# MCU.net
KiCad netlist of a schematic drawn in Altium Designer
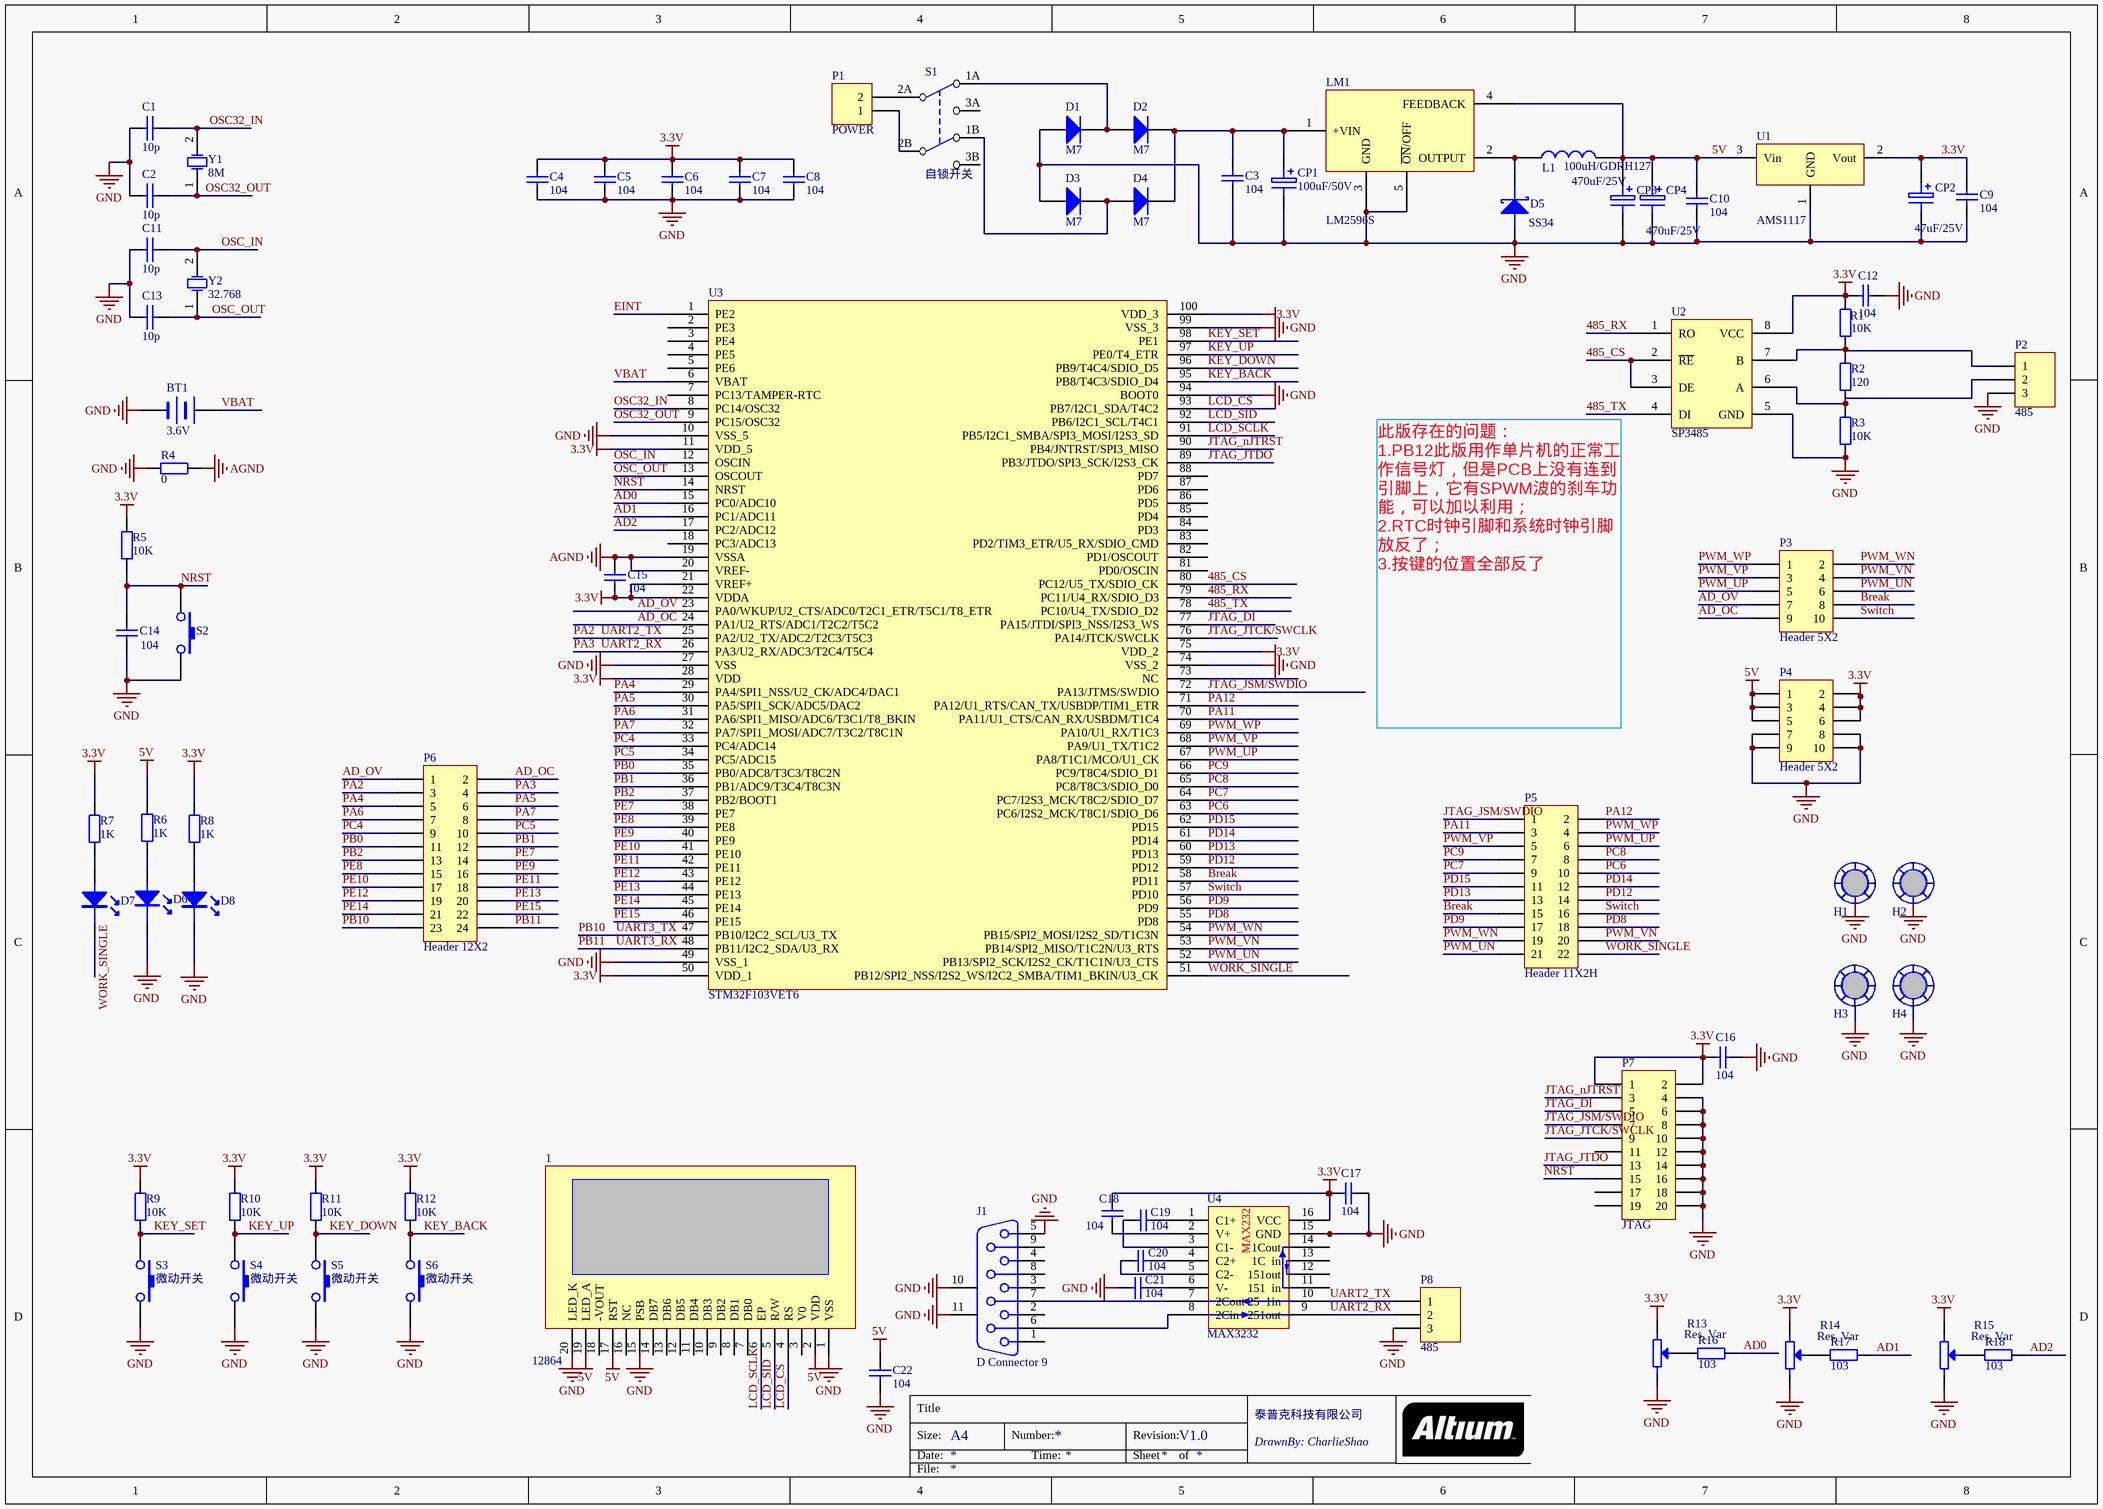
[diagram p0: MCU外围电路.SchDoc]

(export (version "E")
  (design (tool "Eeschema 10.0.6"))
  (components
    (comp (ref "1") (value "12864") (footprint "YX12864B") (libsource (lib "Backup of 杨飞原理库") (part "12864")))
    (comp (ref "BT1")
      (value "3.6V")
      (footprint "CR1220")
      (description "3.6V纽扣电池")
      (libsource (lib "cloudlib") (part "BATTERY"))
    )
    (comp (ref "C1")
      (value "10p")
      (footprint "0805C")
      (description "非极性电容")
      (libsource (lib "cloudlib") (part "Cap"))
    )
    (comp (ref "C2")
      (value "10p")
      (footprint "0805C")
      (description "非极性电容")
      (libsource (lib "cloudlib") (part "Cap"))
    )
    (comp (ref "C3")
      (value "104")
      (footprint "0805C")
      (description "Capacitor")
      (fields (field (name "PUBLISHER") "Altium Limited"))
      (libsource (lib "Miscellaneous Devices") (part "Cap"))
    )
    (comp (ref "C4")
      (value "104")
      (footprint "0805C")
      (description "Capacitor")
      (fields (field (name "PUBLISHER") "Altium Limited"))
      (libsource (lib "Miscellaneous Devices") (part "Cap"))
    )
    (comp (ref "C5")
      (value "104")
      (footprint "0805C")
      (description "Capacitor")
      (fields (field (name "PUBLISHER") "Altium Limited"))
      (libsource (lib "Miscellaneous Devices") (part "Cap"))
    )
    (comp (ref "C6")
      (value "104")
      (footprint "0805C")
      (description "Capacitor")
      (fields (field (name "PUBLISHER") "Altium Limited"))
      (libsource (lib "Miscellaneous Devices") (part "Cap"))
    )
    (comp (ref "C7")
      (value "104")
      (footprint "0805C")
      (description "Capacitor")
      (fields (field (name "PUBLISHER") "Altium Limited"))
      (libsource (lib "Miscellaneous Devices") (part "Cap"))
    )
    (comp (ref "C8")
      (value "104")
      (footprint "0805C")
      (description "Capacitor")
      (fields (field (name "PUBLISHER") "Altium Limited"))
      (libsource (lib "Miscellaneous Devices") (part "Cap"))
    )
    (comp (ref "C9")
      (value "104")
      (footprint "0805C")
      (description "Capacitor")
      (fields (field (name "PUBLISHER") "Altium Limited"))
      (libsource (lib "Miscellaneous Devices") (part "Cap"))
    )
    (comp (ref "C10")
      (value "104")
      (footprint "0805C")
      (description "Capacitor")
      (fields (field (name "PUBLISHER") "Altium Limited"))
      (libsource (lib "Miscellaneous Devices") (part "Cap"))
    )
    (comp (ref "C11")
      (value "10p")
      (footprint "0805C")
      (description "非极性电容")
      (libsource (lib "cloudlib") (part "Cap"))
    )
    (comp (ref "C12")
      (value "104")
      (footprint "0805C")
      (description "Capacitor")
      (fields (field (name "PUBLISHER") "Altium Limited"))
      (libsource (lib "Miscellaneous Devices") (part "Cap"))
    )
    (comp (ref "C13")
      (value "10p")
      (footprint "0805C")
      (description "非极性电容")
      (libsource (lib "cloudlib") (part "Cap"))
    )
    (comp (ref "C14")
      (value "104")
      (footprint "0805C")
      (description "Capacitor")
      (fields (field (name "PUBLISHER") "Altium Limited"))
      (libsource (lib "Miscellaneous Devices") (part "Cap"))
    )
    (comp (ref "C15")
      (value "104")
      (footprint "0805C")
      (description "Capacitor")
      (fields (field (name "PUBLISHER") "Altium Limited"))
      (libsource (lib "Miscellaneous Devices") (part "Cap"))
    )
    (comp (ref "C16")
      (value "104")
      (footprint "0805C")
      (description "Capacitor")
      (fields (field (name "PUBLISHER") "Altium Limited"))
      (libsource (lib "Miscellaneous Devices") (part "Cap"))
    )
    (comp (ref "C17")
      (value "104")
      (footprint "0805C")
      (description "Capacitor")
      (fields (field (name "PUBLISHER") "Altium Limited"))
      (libsource (lib "Miscellaneous Devices") (part "Cap"))
    )
    (comp (ref "C18")
      (value "104")
      (footprint "0805C")
      (description "Capacitor")
      (fields (field (name "PUBLISHER") "Altium Limited"))
      (libsource (lib "Miscellaneous Devices") (part "Cap"))
    )
    (comp (ref "C19")
      (value "104")
      (footprint "0805C")
      (description "Capacitor")
      (fields (field (name "PUBLISHER") "Altium Limited"))
      (libsource (lib "Miscellaneous Devices") (part "Cap"))
    )
    (comp (ref "C20")
      (value "104")
      (footprint "0805C")
      (description "Capacitor")
      (fields (field (name "PUBLISHER") "Altium Limited"))
      (libsource (lib "Miscellaneous Devices") (part "Cap"))
    )
    (comp (ref "C21")
      (value "104")
      (footprint "0805C")
      (description "Capacitor")
      (fields (field (name "PUBLISHER") "Altium Limited"))
      (libsource (lib "Miscellaneous Devices") (part "Cap"))
    )
    (comp (ref "C22")
      (value "104")
      (footprint "0805C")
      (description "Capacitor")
      (fields (field (name "PUBLISHER") "Altium Limited"))
      (libsource (lib "Miscellaneous Devices") (part "Cap"))
    )
    (comp (ref "CP1")
      (value "100uF/50V")
      (footprint "cloudlib:CAP_8X105")
      (description "极性电容")
      (libsource (lib "cloudlib") (part "Cap_Pol"))
    )
    (comp (ref "CP2")
      (value "47uF/25V")
      (footprint "cloudlib:CAP_6.3X5.4")
      (description "极性电容")
      (libsource (lib "cloudlib") (part "Cap_Pol"))
    )
    (comp (ref "CP3")
      (value "470uF/25V")
      (footprint "cloudlib:CAP_10X105")
      (description "极性电容")
      (libsource (lib "cloudlib") (part "Cap_Pol"))
    )
    (comp (ref "CP4")
      (value "470uF/25V")
      (footprint "cloudlib:CAP_10X105")
      (description "极性电容")
      (libsource (lib "cloudlib") (part "Cap_Pol"))
    )
    (comp (ref "D1")
      (value "M7")
      (footprint "SMA")
      (description "Default Diode")
      (fields (field (name "PUBLISHER") "Altium Limited"))
      (libsource (lib "Miscellaneous Devices") (part "Diode"))
    )
    (comp (ref "D2")
      (value "M7")
      (footprint "SMA")
      (description "Default Diode")
      (fields (field (name "PUBLISHER") "Altium Limited"))
      (libsource (lib "Miscellaneous Devices") (part "Diode"))
    )
    (comp (ref "D3")
      (value "M7")
      (footprint "SMA")
      (description "Default Diode")
      (fields (field (name "PUBLISHER") "Altium Limited"))
      (libsource (lib "Miscellaneous Devices") (part "Diode"))
    )
    (comp (ref "D4")
      (value "M7")
      (footprint "SMA")
      (description "Default Diode")
      (fields (field (name "PUBLISHER") "Altium Limited"))
      (libsource (lib "Miscellaneous Devices") (part "Diode"))
    )
    (comp (ref "D5")
      (value "SS34")
      (footprint "cloudlib:SMC")
      (description "肖特基")
      (libsource (lib "cloudlib") (part "Diode_Schottky"))
    )
    (comp (ref "D6") (value "LED") (footprint "cloudlib:LED_0805") (libsource (lib "CCDXPLIB") (part "LED")))
    (comp (ref "D7") (value "LED") (footprint "cloudlib:LED_0805") (libsource (lib "CCDXPLIB") (part "LED")))
    (comp (ref "D8") (value "LED") (footprint "cloudlib:LED_0805") (libsource (lib "CCDXPLIB") (part "LED")))
    (comp (ref "H1") (value "铜柱孔") (footprint "HOLE") (libsource (lib "cloudlib") (part "铜柱孔")))
    (comp (ref "H2") (value "铜柱孔") (footprint "HOLE") (libsource (lib "cloudlib") (part "铜柱孔")))
    (comp (ref "H3") (value "铜柱孔") (footprint "HOLE") (libsource (lib "cloudlib") (part "铜柱孔")))
    (comp (ref "H4") (value "铜柱孔") (footprint "HOLE") (libsource (lib "cloudlib") (part "铜柱孔")))
    (comp (ref "J1")
      (value "D Connector 9")
      (footprint "DSUB1.385-2H9")
      (description "Receptacle Assembly, 9 Position, Right Angle")
      (fields (field (name "PUBLISHER") "Altium Limited"))
      (libsource (lib "Miscellaneous Connectors") (part "D Connector 9"))
    )
    (comp (ref "L1")
      (value "100uH/GDRH127")
      (footprint "cloudlib:SMDRH124/125/127")
      (description "电感")
      (libsource (lib "cloudlib") (part "Inductor"))
    )
    (comp (ref "LM1") (value "LM2596S") (footprint "TO-263S") (libsource (lib "cloudlib") (part "LM2596S")))
    (comp (ref "P1")
      (value "POWER")
      (footprint "cloudlib:3.81-2")
      (description "Header, 2-Pin")
      (fields (field (name "PUBLISHER") "Altium Limited"))
      (libsource (lib "Miscellaneous Connectors") (part "Header 2"))
    )
    (comp (ref "P2")
      (value "485")
      (footprint "cloudlib:SIP3")
      (description "Header, 3-Pin")
      (fields (field (name "PUBLISHER") "Altium Limited"))
      (libsource (lib "Miscellaneous Connectors") (part "MHDR1X3"))
    )
    (comp (ref "P3")
      (value "Header 5X2")
      (footprint "HDR2X5")
      (description "Header, 5-Pin, Dual row")
      (fields (field (name "PUBLISHER") "Altium Limited"))
      (libsource (lib "Miscellaneous Connectors") (part "Header 5X2"))
    )
    (comp (ref "P4")
      (value "Header 5X2")
      (footprint "HDR2X5")
      (description "Header, 5-Pin, Dual row")
      (fields (field (name "PUBLISHER") "Altium Limited"))
      (libsource (lib "Miscellaneous Connectors") (part "Header 5X2"))
    )
    (comp (ref "P5")
      (value "Header 11X2H")
      (footprint "Miscellaneous Connectors:HDR2X11")
      (description "Header, 11-Pin, Dual row, Right Angle")
      (fields (field (name "PUBLISHER") "Altium Limited"))
      (libsource (lib "Miscellaneous Connectors") (part "Header 11X2H"))
    )
    (comp (ref "P6")
      (value "Header 12X2")
      (footprint "HDR2X12")
      (description "Header, 12-Pin, Dual row")
      (fields (field (name "PUBLISHER") "Altium Limited"))
      (libsource (lib "Miscellaneous Connectors") (part "Header 12X2"))
    )
    (comp (ref "P7")
      (value "JTAG")
      (footprint "JTAG20")
      (description "Header, 10-Pin, Dual row")
      (fields (field (name "PUBLISHER") "Altium Limited"))
      (libsource (lib "Miscellaneous Connectors") (part "Header 10X2"))
    )
    (comp (ref "P8")
      (value "485")
      (footprint "cloudlib:SIP3")
      (description "Header, 3-Pin")
      (fields (field (name "PUBLISHER") "Altium Limited"))
      (libsource (lib "Miscellaneous Connectors") (part "MHDR1X3"))
    )
    (comp (ref "R1")
      (value "10K")
      (footprint "0805R")
      (description "Resistor")
      (fields (field (name "PUBLISHER") "Altium Limited"))
      (libsource (lib "") (part "Res2_2"))
    )
    (comp (ref "R2")
      (value "120")
      (footprint "0805R")
      (description "Resistor")
      (fields (field (name "PUBLISHER") "Altium Limited"))
      (libsource (lib "") (part "Res2_2"))
    )
    (comp (ref "R3")
      (value "10K")
      (footprint "0805R")
      (description "Resistor")
      (fields (field (name "PUBLISHER") "Altium Limited"))
      (libsource (lib "") (part "Res2_2"))
    )
    (comp (ref "R4")
      (value "0")
      (footprint "0805R")
      (description "Resistor")
      (fields (field (name "PUBLISHER") "Altium Limited"))
      (libsource (lib "") (part "Res2_1"))
    )
    (comp (ref "R5")
      (value "10K")
      (footprint "0805R")
      (description "Resistor")
      (fields (field (name "PUBLISHER") "Altium Limited"))
      (libsource (lib "") (part "Res2_2"))
    )
    (comp (ref "R6")
      (value "1K")
      (footprint "0805R")
      (description "Resistor")
      (fields (field (name "PUBLISHER") "Altium Limited"))
      (libsource (lib "Miscellaneous Devices") (part "Res2"))
    )
    (comp (ref "R7")
      (value "1K")
      (footprint "0805R")
      (description "Resistor")
      (fields (field (name "PUBLISHER") "Altium Limited"))
      (libsource (lib "Miscellaneous Devices") (part "Res2"))
    )
    (comp (ref "R8")
      (value "1K")
      (footprint "0805R")
      (description "Resistor")
      (fields (field (name "PUBLISHER") "Altium Limited"))
      (libsource (lib "Miscellaneous Devices") (part "Res2"))
    )
    (comp (ref "R9")
      (value "10K")
      (footprint "0805R")
      (description "Resistor")
      (fields (field (name "PUBLISHER") "Altium Limited"))
      (libsource (lib "") (part "Res2_2"))
    )
    (comp (ref "R10")
      (value "10K")
      (footprint "0805R")
      (description "Resistor")
      (fields (field (name "PUBLISHER") "Altium Limited"))
      (libsource (lib "") (part "Res2_2"))
    )
    (comp (ref "R11")
      (value "10K")
      (footprint "0805R")
      (description "Resistor")
      (fields (field (name "PUBLISHER") "Altium Limited"))
      (libsource (lib "") (part "Res2_2"))
    )
    (comp (ref "R12")
      (value "10K")
      (footprint "0805R")
      (description "Resistor")
      (fields (field (name "PUBLISHER") "Altium Limited"))
      (libsource (lib "") (part "Res2_2"))
    )
    (comp (ref "R13")
      (value "Res_Var")
      (footprint "cloudlib:VR1")
      (description "可变电阻")
      (libsource (lib "cloudlib") (part "Res_Var"))
    )
    (comp (ref "R14")
      (value "Res_Var")
      (footprint "cloudlib:VR1")
      (description "可变电阻")
      (libsource (lib "cloudlib") (part "Res_Var"))
    )
    (comp (ref "R15")
      (value "Res_Var")
      (footprint "cloudlib:VR1")
      (description "可变电阻")
      (libsource (lib "cloudlib") (part "Res_Var"))
    )
    (comp (ref "R16")
      (value "103")
      (footprint "cloudlib:0805R")
      (description "Resistor")
      (fields (field (name "PUBLISHER") "Altium Limited"))
      (libsource (lib "") (part "Res2_1"))
    )
    (comp (ref "R17")
      (value "103")
      (footprint "cloudlib:0805R")
      (description "Resistor")
      (fields (field (name "PUBLISHER") "Altium Limited"))
      (libsource (lib "") (part "Res2_1"))
    )
    (comp (ref "R18")
      (value "103")
      (footprint "cloudlib:0805R")
      (description "Resistor")
      (fields (field (name "PUBLISHER") "Altium Limited"))
      (libsource (lib "") (part "Res2_1"))
    )
    (comp (ref "S1") (value "自锁开关") (footprint "cloudlib:自锁开关") (libsource (lib "cloudlib") (part "自锁开关")))
    (comp (ref "S2")
      (value "KEY")
      (footprint "cloudlib:SW_PB - 6.5x4.5")
      (libsource (lib "CCDXPLIB") (part "KEY"))
    )
    (comp (ref "S3")
      (value "微动开关")
      (footprint "cloudlib:SW_PB - 6.5x4.5")
      (libsource (lib "开关") (part "微动开关"))
    )
    (comp (ref "S4")
      (value "微动开关")
      (footprint "cloudlib:SW_PB - 6.5x4.5")
      (libsource (lib "开关") (part "微动开关"))
    )
    (comp (ref "S5")
      (value "微动开关")
      (footprint "cloudlib:SW_PB - 6.5x4.5")
      (libsource (lib "开关") (part "微动开关"))
    )
    (comp (ref "S6")
      (value "微动开关")
      (footprint "cloudlib:SW_PB - 6.5x4.5")
      (libsource (lib "开关") (part "微动开关"))
    )
    (comp (ref "U1")
      (value "AMS1117")
      (footprint "SOT223")
      (description "三端稳压器件")
      (libsource (lib "cloudlib") (part "AMS1117"))
    )
    (comp (ref "U2") (value "SP3485") (footprint "myall:SO-8") (libsource (lib "cloudlib") (part "MAX485")))
    (comp (ref "U3")
      (value "STM32F103VET6")
      (footprint "cloudlib:LQFP100")
      (libsource (lib "cloudlib") (part "STM32F103VET6"))
    )
    (comp (ref "U4")
      (value "MAX3232")
      (footprint "cloudlib:SO-16")
      (libsource (lib "单片机及相关") (part "MAX232"))
    )
    (comp (ref "Y1")
      (value "8M")
      (footprint "XTAL2")
      (description "Crystal Oscillator")
      (fields (field (name "PUBLISHER") "Altium Limited"))
      (libsource (lib "cloudlib") (part "XTAL"))
    )
    (comp (ref "Y2")
      (value "32.768")
      (footprint "XTAL1")
      (description "Crystal Oscillator")
      (fields (field (name "PUBLISHER") "Altium Limited"))
      (libsource (lib "cloudlib") (part "XTAL"))
    )
  )
  (nets
    (net (code "1") (name "/485_CS") (class "Default")
      (node (ref "U2") (pin "2") (pinfunction "~{RE}_2") (pintype "open_emitter"))
      (node (ref "U2") (pin "3") (pinfunction "DE_3") (pintype "open_emitter"))
      (node (ref "U3") (pin "80") (pinfunction "PC12/U5_TX/SDIO_CK_80") (pintype "passive"))
    )
    (net (code "2") (name "/485_RX") (class "Default")
      (node (ref "U2") (pin "1") (pinfunction "RO_1") (pintype "open_emitter"))
      (node (ref "U3") (pin "79") (pinfunction "PC11/U4_RX/SDIO_D3_79") (pintype "passive"))
    )
    (net (code "3") (name "/485_TX") (class "Default")
      (node (ref "U2") (pin "4") (pinfunction "DI_4") (pintype "open_emitter"))
      (node (ref "U3") (pin "78") (pinfunction "PC10/U4_TX/SDIO_D2_78") (pintype "passive"))
    )
    (net (code "4") (name "/AD0") (class "Default")
      (node (ref "R16") (pin "1") (pinfunction "1_1") (pintype "passive"))
      (node (ref "U3") (pin "15") (pinfunction "PC0/ADC10_15") (pintype "passive"))
    )
    (net (code "5") (name "/AD1") (class "Default")
      (node (ref "R17") (pin "1") (pinfunction "1_1") (pintype "passive"))
      (node (ref "U3") (pin "16") (pinfunction "PC1/ADC11_16") (pintype "passive"))
    )
    (net (code "6") (name "/AD2") (class "Default")
      (node (ref "R18") (pin "1") (pinfunction "1_1") (pintype "passive"))
      (node (ref "U3") (pin "17") (pinfunction "PC2/ADC12_17") (pintype "passive"))
    )
    (net (code "7") (name "/AD_OC") (class "Default")
      (node (ref "P3") (pin "9") (pinfunction "9_9") (pintype "passive"))
      (node (ref "P6") (pin "2") (pinfunction "2_2") (pintype "passive"))
      (node (ref "U3") (pin "24") (pinfunction "PA1/U2_RTS/ADC1/T2C2/T5C2_24") (pintype "passive"))
    )
    (net (code "8") (name "/AD_OV") (class "Default")
      (node (ref "P3") (pin "7") (pinfunction "7_7") (pintype "passive"))
      (node (ref "P6") (pin "1") (pinfunction "1_1") (pintype "passive"))
      (node (ref "U3") (pin "23") (pinfunction "PA0/WKUP/U2_CTS/ADC0/T2C1_ETR/T5C1/T8_ETR_23") (pintype "passive"))
    )
    (net (code "9") (name "/Break") (class "Default")
      (node (ref "P3") (pin "8") (pinfunction "8_8") (pintype "passive"))
      (node (ref "P5") (pin "15") (pinfunction "15_15") (pintype "passive"))
      (node (ref "U3") (pin "58") (pinfunction "PD11_58") (pintype "passive"))
    )
    (net (code "10") (name "/EINT") (class "Default")
      (node (ref "U3") (pin "1") (pinfunction "PE2_1") (pintype "passive"))
    )
    (net (code "11") (name "/JTAG_DI") (class "Default")
      (node (ref "P7") (pin "5") (pinfunction "5_5") (pintype "passive"))
      (node (ref "U3") (pin "77") (pinfunction "PA15/JTDI/SPI3_NSS/I2S3_WS_77") (pintype "passive"))
    )
    (net (code "12") (name "/JTAG_JSM{slash}SWDIO") (class "Default")
      (node (ref "P5") (pin "1") (pinfunction "1_1") (pintype "passive"))
      (node (ref "P7") (pin "7") (pinfunction "7_7") (pintype "passive"))
      (node (ref "U3") (pin "72") (pinfunction "PA13/JTMS/SWDIO_72") (pintype "passive"))
    )
    (net (code "13") (name "/JTAG_JTCK{slash}SWCLK") (class "Default")
      (node (ref "P7") (pin "9") (pinfunction "9_9") (pintype "passive"))
      (node (ref "U3") (pin "76") (pinfunction "PA14/JTCK/SWCLK_76") (pintype "passive"))
    )
    (net (code "14") (name "/JTAG_JTDO") (class "Default")
      (node (ref "P7") (pin "13") (pinfunction "13_13") (pintype "passive"))
      (node (ref "U3") (pin "89") (pinfunction "PB3/JTDO/SPI3_SCK/I2S3_CK_89") (pintype "passive"))
    )
    (net (code "15") (name "/JTAG_nJTRST") (class "Default")
      (node (ref "P7") (pin "3") (pinfunction "3_3") (pintype "passive"))
      (node (ref "U3") (pin "90") (pinfunction "PB4/JNTRST/SPI3_MISO_90") (pintype "passive"))
    )
    (net (code "16") (name "/KEY_BACK") (class "Default")
      (node (ref "R12") (pin "1") (pinfunction "1_1") (pintype "passive"))
      (node (ref "S6") (pin "1") (pinfunction "1_1") (pintype "passive"))
      (node (ref "U3") (pin "95") (pinfunction "PB8/T4C3/SDIO_D4_95") (pintype "passive"))
    )
    (net (code "17") (name "/KEY_DOWN") (class "Default")
      (node (ref "R11") (pin "1") (pinfunction "1_1") (pintype "passive"))
      (node (ref "S5") (pin "1") (pinfunction "1_1") (pintype "passive"))
      (node (ref "U3") (pin "96") (pinfunction "PB9/T4C4/SDIO_D5_96") (pintype "passive"))
    )
    (net (code "18") (name "/KEY_SET") (class "Default")
      (node (ref "R9") (pin "1") (pinfunction "1_1") (pintype "passive"))
      (node (ref "S3") (pin "1") (pinfunction "1_1") (pintype "passive"))
      (node (ref "U3") (pin "98") (pinfunction "PE1_98") (pintype "passive"))
    )
    (net (code "19") (name "/KEY_UP") (class "Default")
      (node (ref "R10") (pin "1") (pinfunction "1_1") (pintype "passive"))
      (node (ref "S4") (pin "1") (pinfunction "1_1") (pintype "passive"))
      (node (ref "U3") (pin "97") (pinfunction "PE0/T4_ETR_97") (pintype "passive"))
    )
    (net (code "20") (name "/LCD_CS") (class "Default")
      (node (ref "1") (pin "4") (pinfunction "RS_4") (pintype "passive"))
      (node (ref "U3") (pin "93") (pinfunction "PB7/I2C1_SDA/T4C2_93") (pintype "passive"))
    )
    (net (code "21") (name "/LCD_SCLK") (class "Default")
      (node (ref "1") (pin "6") (pinfunction "EP_6") (pintype "passive"))
      (node (ref "U3") (pin "91") (pinfunction "PB5/I2C1_SMBA/SPI3_MOSI/I2S3_SD_91") (pintype "passive"))
    )
    (net (code "22") (name "/LCD_SID") (class "Default")
      (node (ref "1") (pin "5") (pinfunction "R/W_5") (pintype "passive"))
      (node (ref "U3") (pin "92") (pinfunction "PB6/I2C1_SCL/T4C1_92") (pintype "passive"))
    )
    (net (code "23") (name "/NRST") (class "Default")
      (node (ref "C14") (pin "2") (pinfunction "2_2") (pintype "passive"))
      (node (ref "P7") (pin "15") (pinfunction "15_15") (pintype "passive"))
      (node (ref "R5") (pin "1") (pinfunction "1_1") (pintype "passive"))
      (node (ref "S2") (pin "1") (pinfunction "1_1") (pintype "passive"))
      (node (ref "U3") (pin "14") (pinfunction "NRST_14") (pintype "passive"))
    )
    (net (code "24") (name "/OSC32_IN") (class "Default")
      (node (ref "C1") (pin "2") (pinfunction "2_2") (pintype "passive"))
      (node (ref "U3") (pin "8") (pinfunction "PC14/OSC32_8") (pintype "passive"))
      (node (ref "Y1") (pin "2") (pinfunction "OSC2_2") (pintype "passive"))
    )
    (net (code "25") (name "/OSC32_OUT") (class "Default")
      (node (ref "C2") (pin "2") (pinfunction "2_2") (pintype "passive"))
      (node (ref "U3") (pin "9") (pinfunction "PC15/OSC32_9") (pintype "passive"))
      (node (ref "Y1") (pin "1") (pinfunction "OSC1_1") (pintype "passive"))
    )
    (net (code "26") (name "/OSC_IN") (class "Default")
      (node (ref "C11") (pin "2") (pinfunction "2_2") (pintype "passive"))
      (node (ref "U3") (pin "12") (pinfunction "OSCIN_12") (pintype "passive"))
      (node (ref "Y2") (pin "2") (pinfunction "OSC2_2") (pintype "passive"))
    )
    (net (code "27") (name "/OSC_OUT") (class "Default")
      (node (ref "C13") (pin "2") (pinfunction "2_2") (pintype "passive"))
      (node (ref "U3") (pin "13") (pinfunction "OSCOUT_13") (pintype "passive"))
      (node (ref "Y2") (pin "1") (pinfunction "OSC1_1") (pintype "passive"))
    )
    (net (code "28") (name "/PA2") (class "Default")
      (node (ref "P6") (pin "3") (pinfunction "3_3") (pintype "passive"))
      (node (ref "P8") (pin "1") (pinfunction "1_1") (pintype "passive"))
      (node (ref "U3") (pin "25") (pinfunction "PA2/U2_TX/ADC2/T2C3/T5C3_25") (pintype "passive"))
      (node (ref "U4") (pin "10") (pinfunction "25__1in_10") (pintype "passive"))
    )
    (net (code "29") (name "/PA3") (class "Default")
      (node (ref "P6") (pin "4") (pinfunction "4_4") (pintype "passive"))
      (node (ref "P8") (pin "2") (pinfunction "2_2") (pintype "passive"))
      (node (ref "U3") (pin "26") (pinfunction "PA3/U2_RX/ADC3/T2C4/T5C4_26") (pintype "passive"))
      (node (ref "U4") (pin "9") (pinfunction "251out_9") (pintype "passive"))
    )
    (net (code "30") (name "/PA4") (class "Default")
      (node (ref "P6") (pin "5") (pinfunction "5_5") (pintype "passive"))
      (node (ref "U3") (pin "29") (pinfunction "PA4/SPI1_NSS/U2_CK/ADC4/DAC1_29") (pintype "passive"))
    )
    (net (code "31") (name "/PA5") (class "Default")
      (node (ref "P6") (pin "6") (pinfunction "6_6") (pintype "passive"))
      (node (ref "U3") (pin "30") (pinfunction "PA5/SPI1_SCK/ADC5/DAC2_30") (pintype "passive"))
    )
    (net (code "32") (name "/PA6") (class "Default")
      (node (ref "P6") (pin "7") (pinfunction "7_7") (pintype "passive"))
      (node (ref "U3") (pin "31") (pinfunction "PA6/SPI1_MISO/ADC6/T3C1/T8_BKIN_31") (pintype "passive"))
    )
    (net (code "33") (name "/PA7") (class "Default")
      (node (ref "P6") (pin "8") (pinfunction "8_8") (pintype "passive"))
      (node (ref "U3") (pin "32") (pinfunction "PA7/SPI1_MOSI/ADC7/T3C2/T8C1N_32") (pintype "passive"))
    )
    (net (code "34") (name "/PA11") (class "Default")
      (node (ref "P5") (pin "3") (pinfunction "3_3") (pintype "passive"))
      (node (ref "U3") (pin "70") (pinfunction "PA11/U1_CTS/CAN_RX/USBDM/T1C4_70") (pintype "passive"))
    )
    (net (code "35") (name "/PA12") (class "Default")
      (node (ref "P5") (pin "2") (pinfunction "2_2") (pintype "passive"))
      (node (ref "U3") (pin "71") (pinfunction "PA12/U1_RTS/CAN_TX/USBDP/TIM1_ETR_71") (pintype "passive"))
    )
    (net (code "36") (name "/PB0") (class "Default")
      (node (ref "P6") (pin "11") (pinfunction "11_11") (pintype "passive"))
      (node (ref "U3") (pin "35") (pinfunction "PB0/ADC8/T3C3/T8C2N_35") (pintype "passive"))
    )
    (net (code "37") (name "/PB1") (class "Default")
      (node (ref "P6") (pin "12") (pinfunction "12_12") (pintype "passive"))
      (node (ref "U3") (pin "36") (pinfunction "PB1/ADC9/T3C4/T8C3N_36") (pintype "passive"))
    )
    (net (code "38") (name "/PB2") (class "Default")
      (node (ref "P6") (pin "13") (pinfunction "13_13") (pintype "passive"))
      (node (ref "U3") (pin "37") (pinfunction "PB2/BOOT1_37") (pintype "passive"))
    )
    (net (code "39") (name "/PB10") (class "Default")
      (node (ref "P6") (pin "23") (pinfunction "23_23") (pintype "passive"))
      (node (ref "U3") (pin "47") (pinfunction "PB10/I2C2_SCL/U3_TX_47") (pintype "passive"))
    )
    (net (code "40") (name "/PB11") (class "Default")
      (node (ref "P6") (pin "24") (pinfunction "24_24") (pintype "passive"))
      (node (ref "U3") (pin "48") (pinfunction "PB11/I2C2_SDA/U3_RX_48") (pintype "passive"))
    )
    (net (code "41") (name "/PC4") (class "Default")
      (node (ref "P6") (pin "9") (pinfunction "9_9") (pintype "passive"))
      (node (ref "U3") (pin "33") (pinfunction "PC4/ADC14_33") (pintype "passive"))
    )
    (net (code "42") (name "/PC5") (class "Default")
      (node (ref "P6") (pin "10") (pinfunction "10_10") (pintype "passive"))
      (node (ref "U3") (pin "34") (pinfunction "PC5/ADC15_34") (pintype "passive"))
    )
    (net (code "43") (name "/PC6") (class "Default")
      (node (ref "P5") (pin "10") (pinfunction "10_10") (pintype "passive"))
      (node (ref "U3") (pin "63") (pinfunction "PC6/I2S2_MCK/T8C1/SDIO_D6_63") (pintype "passive"))
    )
    (net (code "44") (name "/PC7") (class "Default")
      (node (ref "P5") (pin "9") (pinfunction "9_9") (pintype "passive"))
      (node (ref "U3") (pin "64") (pinfunction "PC7/I2S3_MCK/T8C2/SDIO_D7_64") (pintype "passive"))
    )
    (net (code "45") (name "/PC8") (class "Default")
      (node (ref "P5") (pin "8") (pinfunction "8_8") (pintype "passive"))
      (node (ref "U3") (pin "65") (pinfunction "PC8/T8C3/SDIO_D0_65") (pintype "passive"))
    )
    (net (code "46") (name "/PC9") (class "Default")
      (node (ref "P5") (pin "7") (pinfunction "7_7") (pintype "passive"))
      (node (ref "U3") (pin "66") (pinfunction "PC9/T8C4/SDIO_D1_66") (pintype "passive"))
    )
    (net (code "47") (name "/PD8") (class "Default")
      (node (ref "P5") (pin "18") (pinfunction "18_18") (pintype "passive"))
      (node (ref "U3") (pin "55") (pinfunction "PD8_55") (pintype "passive"))
    )
    (net (code "48") (name "/PD9") (class "Default")
      (node (ref "P5") (pin "17") (pinfunction "17_17") (pintype "passive"))
      (node (ref "U3") (pin "56") (pinfunction "PD9_56") (pintype "passive"))
    )
    (net (code "49") (name "/PD12") (class "Default")
      (node (ref "P5") (pin "14") (pinfunction "14_14") (pintype "passive"))
      (node (ref "U3") (pin "59") (pinfunction "PD12_59") (pintype "passive"))
    )
    (net (code "50") (name "/PD13") (class "Default")
      (node (ref "P5") (pin "13") (pinfunction "13_13") (pintype "passive"))
      (node (ref "U3") (pin "60") (pinfunction "PD13_60") (pintype "passive"))
    )
    (net (code "51") (name "/PD14") (class "Default")
      (node (ref "P5") (pin "12") (pinfunction "12_12") (pintype "passive"))
      (node (ref "U3") (pin "61") (pinfunction "PD14_61") (pintype "passive"))
    )
    (net (code "52") (name "/PD15") (class "Default")
      (node (ref "P5") (pin "11") (pinfunction "11_11") (pintype "passive"))
      (node (ref "U3") (pin "62") (pinfunction "PD15_62") (pintype "passive"))
    )
    (net (code "53") (name "/PE7") (class "Default")
      (node (ref "P6") (pin "14") (pinfunction "14_14") (pintype "passive"))
      (node (ref "U3") (pin "38") (pinfunction "PE7_38") (pintype "passive"))
    )
    (net (code "54") (name "/PE8") (class "Default")
      (node (ref "P6") (pin "15") (pinfunction "15_15") (pintype "passive"))
      (node (ref "U3") (pin "39") (pinfunction "PE8_39") (pintype "passive"))
    )
    (net (code "55") (name "/PE9") (class "Default")
      (node (ref "P6") (pin "16") (pinfunction "16_16") (pintype "passive"))
      (node (ref "U3") (pin "40") (pinfunction "PE9_40") (pintype "passive"))
    )
    (net (code "56") (name "/PE10") (class "Default")
      (node (ref "P6") (pin "17") (pinfunction "17_17") (pintype "passive"))
      (node (ref "U3") (pin "41") (pinfunction "PE10_41") (pintype "passive"))
    )
    (net (code "57") (name "/PE11") (class "Default")
      (node (ref "P6") (pin "18") (pinfunction "18_18") (pintype "passive"))
      (node (ref "U3") (pin "42") (pinfunction "PE11_42") (pintype "passive"))
    )
    (net (code "58") (name "/PE12") (class "Default")
      (node (ref "P6") (pin "19") (pinfunction "19_19") (pintype "passive"))
      (node (ref "U3") (pin "43") (pinfunction "PE12_43") (pintype "passive"))
    )
    (net (code "59") (name "/PE13") (class "Default")
      (node (ref "P6") (pin "20") (pinfunction "20_20") (pintype "passive"))
      (node (ref "U3") (pin "44") (pinfunction "PE13_44") (pintype "passive"))
    )
    (net (code "60") (name "/PE14") (class "Default")
      (node (ref "P6") (pin "21") (pinfunction "21_21") (pintype "passive"))
      (node (ref "U3") (pin "45") (pinfunction "PE14_45") (pintype "passive"))
    )
    (net (code "61") (name "/PE15") (class "Default")
      (node (ref "P6") (pin "22") (pinfunction "22_22") (pintype "passive"))
      (node (ref "U3") (pin "46") (pinfunction "PE15_46") (pintype "passive"))
    )
    (net (code "62") (name "/PWM_UN") (class "Default")
      (node (ref "P3") (pin "6") (pinfunction "6_6") (pintype "passive"))
      (node (ref "P5") (pin "21") (pinfunction "21_21") (pintype "passive"))
      (node (ref "U3") (pin "52") (pinfunction "PB13/SPI2_SCK/I2S2_CK/T1C1N/U3_CTS_52") (pintype "passive"))
    )
    (net (code "63") (name "/PWM_UP") (class "Default")
      (node (ref "P3") (pin "5") (pinfunction "5_5") (pintype "passive"))
      (node (ref "P5") (pin "6") (pinfunction "6_6") (pintype "passive"))
      (node (ref "U3") (pin "67") (pinfunction "PA8/T1C1/MCO/U1_CK_67") (pintype "passive"))
    )
    (net (code "64") (name "/PWM_VN") (class "Default")
      (node (ref "P3") (pin "4") (pinfunction "4_4") (pintype "passive"))
      (node (ref "P5") (pin "20") (pinfunction "20_20") (pintype "passive"))
      (node (ref "U3") (pin "53") (pinfunction "PB14/SPI2_MISO/T1C2N/U3_RTS_53") (pintype "passive"))
    )
    (net (code "65") (name "/PWM_VP") (class "Default")
      (node (ref "P3") (pin "3") (pinfunction "3_3") (pintype "passive"))
      (node (ref "P5") (pin "5") (pinfunction "5_5") (pintype "passive"))
      (node (ref "U3") (pin "68") (pinfunction "PA9/U1_TX/T1C2_68") (pintype "passive"))
    )
    (net (code "66") (name "/PWM_WN") (class "Default")
      (node (ref "P3") (pin "2") (pinfunction "2_2") (pintype "passive"))
      (node (ref "P5") (pin "19") (pinfunction "19_19") (pintype "passive"))
      (node (ref "U3") (pin "54") (pinfunction "PB15/SPI2_MOSI/I2S2_SD/T1C3N_54") (pintype "passive"))
    )
    (net (code "67") (name "/PWM_WP") (class "Default")
      (node (ref "P3") (pin "1") (pinfunction "1_1") (pintype "passive"))
      (node (ref "P5") (pin "4") (pinfunction "4_4") (pintype "passive"))
      (node (ref "U3") (pin "69") (pinfunction "PA10/U1_RX/T1C3_69") (pintype "passive"))
    )
    (net (code "68") (name "/Switch") (class "Default")
      (node (ref "P3") (pin "10") (pinfunction "10_10") (pintype "passive"))
      (node (ref "P5") (pin "16") (pinfunction "16_16") (pintype "passive"))
      (node (ref "U3") (pin "57") (pinfunction "PD10_57") (pintype "passive"))
    )
    (net (code "69") (name "/VBAT") (class "Default")
      (node (ref "BT1") (pin "1") (pinfunction "+_1") (pintype "passive"))
      (node (ref "U3") (pin "6") (pinfunction "VBAT_6") (pintype "passive"))
    )
    (net (code "70") (name "/WORK_SINGLE") (class "Default")
      (node (ref "P5") (pin "22") (pinfunction "22_22") (pintype "passive"))
      (node (ref "U3") (pin "51") (pinfunction "PB12/SPI2_NSS/I2S2_WS/I2C2_SMBA/TIM1_BKIN/U3_CK_51") (pintype "passive"))
    )
    (net (code "71") (name "3.3V") (class "Default")
      (node (ref "C12") (pin "1") (pinfunction "1_1") (pintype "passive"))
      (node (ref "C15") (pin "2") (pinfunction "2_2") (pintype "passive"))
      (node (ref "C16") (pin "1") (pinfunction "1_1") (pintype "passive"))
      (node (ref "C17") (pin "2") (pinfunction "2_2") (pintype "passive"))
      (node (ref "C18") (pin "2") (pinfunction "2_2") (pintype "passive"))
      (node (ref "C4") (pin "1") (pinfunction "1_1") (pintype "passive"))
      (node (ref "C5") (pin "1") (pinfunction "1_1") (pintype "passive"))
      (node (ref "C6") (pin "1") (pinfunction "1_1") (pintype "passive"))
      (node (ref "C7") (pin "1") (pinfunction "1_1") (pintype "passive"))
      (node (ref "C8") (pin "1") (pinfunction "1_1") (pintype "passive"))
      (node (ref "C9") (pin "1") (pinfunction "1_1") (pintype "passive"))
      (node (ref "CP2") (pin "1") (pinfunction "1_1") (pintype "passive"))
      (node (ref "P4") (pin "2") (pinfunction "2_2") (pintype "passive"))
      (node (ref "P4") (pin "4") (pinfunction "4_4") (pintype "passive"))
      (node (ref "P4") (pin "6") (pinfunction "6_6") (pintype "passive"))
      (node (ref "P7") (pin "1") (pinfunction "1_1") (pintype "passive"))
      (node (ref "P7") (pin "2") (pinfunction "2_2") (pintype "passive"))
      (node (ref "R1") (pin "2") (pinfunction "2_2") (pintype "passive"))
      (node (ref "R10") (pin "2") (pinfunction "2_2") (pintype "passive"))
      (node (ref "R11") (pin "2") (pinfunction "2_2") (pintype "passive"))
      (node (ref "R12") (pin "2") (pinfunction "2_2") (pintype "passive"))
      (node (ref "R13") (pin "1") (pinfunction "1_1") (pintype "passive"))
      (node (ref "R14") (pin "1") (pinfunction "1_1") (pintype "passive"))
      (node (ref "R15") (pin "1") (pinfunction "1_1") (pintype "passive"))
      (node (ref "R5") (pin "2") (pinfunction "2_2") (pintype "passive"))
      (node (ref "R7") (pin "1") (pinfunction "1_1") (pintype "passive"))
      (node (ref "R8") (pin "1") (pinfunction "1_1") (pintype "passive"))
      (node (ref "R9") (pin "2") (pinfunction "2_2") (pintype "passive"))
      (node (ref "U1") (pin "2") (pinfunction "Vout_2") (pintype "passive"))
      (node (ref "U2") (pin "8") (pinfunction "VCC_8") (pintype "passive"))
      (node (ref "U3") (pin "100") (pinfunction "VDD_3_100") (pintype "passive"))
      (node (ref "U3") (pin "11") (pinfunction "VDD_5_11") (pintype "passive"))
      (node (ref "U3") (pin "21") (pinfunction "VREF+_21") (pintype "passive"))
      (node (ref "U3") (pin "22") (pinfunction "VDDA_22") (pintype "passive"))
      (node (ref "U3") (pin "28") (pinfunction "VDD_28") (pintype "passive"))
      (node (ref "U3") (pin "50") (pinfunction "VDD_1_50") (pintype "passive"))
      (node (ref "U3") (pin "75") (pinfunction "VDD_2_75") (pintype "passive"))
      (node (ref "U4") (pin "16") (pinfunction "VCC_16") (pintype "passive"))
    )
    (net (code "72") (name "5V") (class "Default")
      (node (ref "1") (pin "17") (pinfunction "RST_17") (pintype "passive"))
      (node (ref "1") (pin "19") (pinfunction "LED_A_19") (pintype "passive"))
      (node (ref "1") (pin "2") (pinfunction "VDD_2") (pintype "passive"))
      (node (ref "C10") (pin "1") (pinfunction "1_1") (pintype "passive"))
      (node (ref "C22") (pin "2") (pinfunction "2_2") (pintype "passive"))
      (node (ref "CP3") (pin "1") (pinfunction "1_1") (pintype "passive"))
      (node (ref "CP4") (pin "1") (pinfunction "1_1") (pintype "passive"))
      (node (ref "L1") (pin "2") (pinfunction "2_2") (pintype "passive"))
      (node (ref "LM1") (pin "4") (pinfunction "FEEDBACK_4") (pintype "passive"))
      (node (ref "P4") (pin "1") (pinfunction "1_1") (pintype "passive"))
      (node (ref "P4") (pin "3") (pinfunction "3_3") (pintype "passive"))
      (node (ref "P4") (pin "5") (pinfunction "5_5") (pintype "passive"))
      (node (ref "R6") (pin "1") (pinfunction "1_1") (pintype "passive"))
      (node (ref "U1") (pin "3") (pinfunction "Vin_3") (pintype "passive"))
    )
    (net (code "73") (name "AGND") (class "Default")
      (node (ref "C15") (pin "1") (pinfunction "1_1") (pintype "passive"))
      (node (ref "R4") (pin "1") (pinfunction "1_1") (pintype "passive"))
      (node (ref "U3") (pin "19") (pinfunction "VSSA_19") (pintype "passive"))
      (node (ref "U3") (pin "20") (pinfunction "VREF-_20") (pintype "passive"))
    )
    (net (code "74") (name "GND") (class "Default")
      (node (ref "1") (pin "1") (pinfunction "VSS_1") (pintype "passive"))
      (node (ref "1") (pin "15") (pinfunction "PSB_15") (pintype "passive"))
      (node (ref "1") (pin "20") (pinfunction "LED_K_20") (pintype "passive"))
      (node (ref "BT1") (pin "2") (pinfunction "-_2") (pintype "passive"))
      (node (ref "C1") (pin "1") (pinfunction "1_1") (pintype "passive"))
      (node (ref "C10") (pin "2") (pinfunction "2_2") (pintype "passive"))
      (node (ref "C11") (pin "1") (pinfunction "1_1") (pintype "passive"))
      (node (ref "C12") (pin "2") (pinfunction "2_2") (pintype "passive"))
      (node (ref "C13") (pin "1") (pinfunction "1_1") (pintype "passive"))
      (node (ref "C14") (pin "1") (pinfunction "1_1") (pintype "passive"))
      (node (ref "C16") (pin "2") (pinfunction "2_2") (pintype "passive"))
      (node (ref "C17") (pin "1") (pinfunction "1_1") (pintype "passive"))
      (node (ref "C2") (pin "1") (pinfunction "1_1") (pintype "passive"))
      (node (ref "C21") (pin "2") (pinfunction "2_2") (pintype "passive"))
      (node (ref "C22") (pin "1") (pinfunction "1_1") (pintype "passive"))
      (node (ref "C3") (pin "2") (pinfunction "2_2") (pintype "passive"))
      (node (ref "C4") (pin "2") (pinfunction "2_2") (pintype "passive"))
      (node (ref "C5") (pin "2") (pinfunction "2_2") (pintype "passive"))
      (node (ref "C6") (pin "2") (pinfunction "2_2") (pintype "passive"))
      (node (ref "C7") (pin "2") (pinfunction "2_2") (pintype "passive"))
      (node (ref "C8") (pin "2") (pinfunction "2_2") (pintype "passive"))
      (node (ref "C9") (pin "2") (pinfunction "2_2") (pintype "passive"))
      (node (ref "CP1") (pin "2") (pinfunction "2_2") (pintype "passive"))
      (node (ref "CP2") (pin "2") (pinfunction "2_2") (pintype "passive"))
      (node (ref "CP3") (pin "2") (pinfunction "2_2") (pintype "passive"))
      (node (ref "CP4") (pin "2") (pinfunction "2_2") (pintype "passive"))
      (node (ref "D1") (pin "1") (pinfunction "A_1") (pintype "passive"))
      (node (ref "D3") (pin "1") (pinfunction "A_1") (pintype "passive"))
      (node (ref "D5") (pin "1") (pinfunction "A_1") (pintype "passive"))
      (node (ref "D6") (pin "2") (pinfunction "2_2") (pintype "passive"))
      (node (ref "D8") (pin "2") (pinfunction "2_2") (pintype "passive"))
      (node (ref "H1") (pin "0") (pinfunction "0_0") (pintype "passive"))
      (node (ref "H2") (pin "0") (pinfunction "0_0") (pintype "passive"))
      (node (ref "H3") (pin "0") (pinfunction "0_0") (pintype "passive"))
      (node (ref "H4") (pin "0") (pinfunction "0_0") (pintype "passive"))
      (node (ref "J1") (pin "10") (pinfunction "MH1_10") (pintype "passive"))
      (node (ref "J1") (pin "11") (pinfunction "MH2_11") (pintype "passive"))
      (node (ref "J1") (pin "5") (pinfunction "5_5") (pintype "passive"))
      (node (ref "LM1") (pin "3") (pinfunction "GND_3") (pintype "passive"))
      (node (ref "LM1") (pin "5") (pinfunction "~{ON}/OFF_5") (pintype "passive"))
      (node (ref "P2") (pin "3") (pinfunction "3_3") (pintype "passive"))
      (node (ref "P4") (pin "10") (pinfunction "10_10") (pintype "passive"))
      (node (ref "P4") (pin "7") (pinfunction "7_7") (pintype "passive"))
      (node (ref "P4") (pin "8") (pinfunction "8_8") (pintype "passive"))
      (node (ref "P4") (pin "9") (pinfunction "9_9") (pintype "passive"))
      (node (ref "P7") (pin "10") (pinfunction "10_10") (pintype "passive"))
      (node (ref "P7") (pin "12") (pinfunction "12_12") (pintype "passive"))
      (node (ref "P7") (pin "14") (pinfunction "14_14") (pintype "passive"))
      (node (ref "P7") (pin "16") (pinfunction "16_16") (pintype "passive"))
      (node (ref "P7") (pin "18") (pinfunction "18_18") (pintype "passive"))
      (node (ref "P7") (pin "20") (pinfunction "20_20") (pintype "passive"))
      (node (ref "P7") (pin "4") (pinfunction "4_4") (pintype "passive"))
      (node (ref "P7") (pin "6") (pinfunction "6_6") (pintype "passive"))
      (node (ref "P7") (pin "8") (pinfunction "8_8") (pintype "passive"))
      (node (ref "P8") (pin "3") (pinfunction "3_3") (pintype "passive"))
      (node (ref "R13") (pin "3") (pinfunction "2_3") (pintype "passive"))
      (node (ref "R14") (pin "3") (pinfunction "2_3") (pintype "passive"))
      (node (ref "R15") (pin "3") (pinfunction "2_3") (pintype "passive"))
      (node (ref "R3") (pin "1") (pinfunction "1_1") (pintype "passive"))
      (node (ref "R4") (pin "2") (pinfunction "2_2") (pintype "passive"))
      (node (ref "S2") (pin "2") (pinfunction "2_2") (pintype "passive"))
      (node (ref "S3") (pin "2") (pinfunction "2_2") (pintype "passive"))
      (node (ref "S4") (pin "2") (pinfunction "2_2") (pintype "passive"))
      (node (ref "S5") (pin "2") (pinfunction "2_2") (pintype "passive"))
      (node (ref "S6") (pin "2") (pinfunction "2_2") (pintype "passive"))
      (node (ref "U1") (pin "1") (pinfunction "GND_1") (pintype "passive"))
      (node (ref "U2") (pin "5") (pinfunction "GND_5") (pintype "passive"))
      (node (ref "U3") (pin "10") (pinfunction "VSS_5_10") (pintype "passive"))
      (node (ref "U3") (pin "27") (pinfunction "VSS_27") (pintype "passive"))
      (node (ref "U3") (pin "49") (pinfunction "VSS_1_49") (pintype "passive"))
      (node (ref "U3") (pin "74") (pinfunction "VSS_2_74") (pintype "passive"))
      (node (ref "U3") (pin "94") (pinfunction "BOOT0_94") (pintype "passive"))
      (node (ref "U3") (pin "99") (pinfunction "VSS_3_99") (pintype "passive"))
      (node (ref "U4") (pin "15") (pinfunction "GND_15") (pintype "passive"))
    )
    (net (code "75") (name "Net-(D1-K)") (class "Default")
      (node (ref "D1") (pin "2") (pinfunction "K_2") (pintype "passive"))
      (node (ref "D2") (pin "1") (pinfunction "A_1") (pintype "passive"))
      (node (ref "S1") (pin "1A") (pinfunction "NC1_1A") (pintype "passive"))
    )
    (net (code "76") (name "Net-(D2-K)") (class "Default")
      (node (ref "C3") (pin "1") (pinfunction "1_1") (pintype "passive"))
      (node (ref "CP1") (pin "1") (pinfunction "1_1") (pintype "passive"))
      (node (ref "D2") (pin "2") (pinfunction "K_2") (pintype "passive"))
      (node (ref "D4") (pin "2") (pinfunction "K_2") (pintype "passive"))
      (node (ref "LM1") (pin "1") (pinfunction "+VIN_1") (pintype "passive"))
    )
    (net (code "77") (name "Net-(D3-K)") (class "Default")
      (node (ref "D3") (pin "2") (pinfunction "K_2") (pintype "passive"))
      (node (ref "D4") (pin "1") (pinfunction "A_1") (pintype "passive"))
      (node (ref "S1") (pin "1B") (pinfunction "NC2_1B") (pintype "passive"))
    )
    (net (code "78") (name "Net-(D5-K)") (class "Default")
      (node (ref "D5") (pin "2") (pinfunction "K_2") (pintype "passive"))
      (node (ref "L1") (pin "1") (pinfunction "1_1") (pintype "passive"))
      (node (ref "LM1") (pin "2") (pinfunction "OUTPUT_2") (pintype "passive"))
    )
    (net (code "79") (name "Net-(D6-Pad1)") (class "Default")
      (node (ref "D6") (pin "1") (pinfunction "1_1") (pintype "passive"))
      (node (ref "R6") (pin "2") (pinfunction "2_2") (pintype "passive"))
    )
    (net (code "80") (name "Net-(D7-Pad1)") (class "Default")
      (node (ref "D7") (pin "1") (pinfunction "1_1") (pintype "passive"))
      (node (ref "R7") (pin "2") (pinfunction "2_2") (pintype "passive"))
    )
    (net (code "81") (name "Net-(D8-Pad1)") (class "Default")
      (node (ref "D8") (pin "1") (pinfunction "1_1") (pintype "passive"))
      (node (ref "R8") (pin "2") (pinfunction "2_2") (pintype "passive"))
    )
    (net (code "82") (name "Net-(R13-W)") (class "Default")
      (node (ref "R13") (pin "2") (pinfunction "W_2") (pintype "passive"))
      (node (ref "R16") (pin "2") (pinfunction "2_2") (pintype "passive"))
    )
    (net (code "83") (name "Net-(R14-W)") (class "Default")
      (node (ref "R14") (pin "2") (pinfunction "W_2") (pintype "passive"))
      (node (ref "R17") (pin "2") (pinfunction "2_2") (pintype "passive"))
    )
    (net (code "84") (name "Net-(R15-W)") (class "Default")
      (node (ref "R15") (pin "2") (pinfunction "W_2") (pintype "passive"))
      (node (ref "R18") (pin "2") (pinfunction "2_2") (pintype "passive"))
    )
    (net (code "85") (name "Net-(S1-COMMON1)") (class "Default")
      (node (ref "P1") (pin "2") (pinfunction "2_2") (pintype "passive"))
      (node (ref "S1") (pin "2A") (pinfunction "COMMON1_2A") (pintype "passive"))
    )
    (net (code "86") (name "Net-(S1-COMMON2)") (class "Default")
      (node (ref "P1") (pin "1") (pinfunction "1_1") (pintype "passive"))
      (node (ref "S1") (pin "2B") (pinfunction "COMMON2_2B") (pintype "passive"))
    )
    (net (code "87") (name "Net-(U2-A)") (class "Default")
      (node (ref "P2") (pin "2") (pinfunction "2_2") (pintype "passive"))
      (node (ref "R2") (pin "1") (pinfunction "1_1") (pintype "passive"))
      (node (ref "R3") (pin "2") (pinfunction "2_2") (pintype "passive"))
      (node (ref "U2") (pin "6") (pinfunction "A_6") (pintype "open_emitter"))
    )
    (net (code "88") (name "Net-(U2-B)") (class "Default")
      (node (ref "P2") (pin "1") (pinfunction "1_1") (pintype "passive"))
      (node (ref "R1") (pin "1") (pinfunction "1_1") (pintype "passive"))
      (node (ref "R2") (pin "2") (pinfunction "2_2") (pintype "passive"))
      (node (ref "U2") (pin "7") (pinfunction "B_7") (pintype "open_emitter"))
    )
    (net (code "89") (name "Net-(U4-2Cin)") (class "Default")
      (node (ref "J1") (pin "6") (pinfunction "6_6") (pintype "passive"))
      (node (ref "U4") (pin "8") (pinfunction "2Cin_8") (pintype "passive"))
    )
    (net (code "90") (name "Net-(U4-2Cout)") (class "Default")
      (node (ref "J1") (pin "7") (pinfunction "7_7") (pintype "passive"))
      (node (ref "U4") (pin "7") (pinfunction "2Cout_7") (pintype "passive"))
    )
    (net (code "91") (name "Net-(U4-C1+)") (class "Default")
      (node (ref "C19") (pin "2") (pinfunction "2_2") (pintype "passive"))
      (node (ref "U4") (pin "1") (pinfunction "C1+_1") (pintype "passive"))
    )
    (net (code "92") (name "Net-(U4-C1-)") (class "Default")
      (node (ref "C19") (pin "1") (pinfunction "1_1") (pintype "passive"))
      (node (ref "U4") (pin "3") (pinfunction "C1-_3") (pintype "passive"))
    )
    (net (code "93") (name "Net-(U4-C2+)") (class "Default")
      (node (ref "C20") (pin "2") (pinfunction "2_2") (pintype "passive"))
      (node (ref "U4") (pin "4") (pinfunction "C2+_4") (pintype "passive"))
    )
    (net (code "94") (name "Net-(U4-C2-)") (class "Default")
      (node (ref "C20") (pin "1") (pinfunction "1_1") (pintype "passive"))
      (node (ref "U4") (pin "5") (pinfunction "C2-_5") (pintype "passive"))
    )
    (net (code "95") (name "Net-(U4-V+)") (class "Default")
      (node (ref "C18") (pin "1") (pinfunction "1_1") (pintype "passive"))
      (node (ref "U4") (pin "2") (pinfunction "V+_2") (pintype "passive"))
    )
    (net (code "96") (name "Net-(U4-V-)") (class "Default")
      (node (ref "C21") (pin "1") (pinfunction "1_1") (pintype "passive"))
      (node (ref "U4") (pin "6") (pinfunction "V-_6") (pintype "passive"))
    )
    (net (code "97") (name "unconnected-(1--VOUT-Pad18)") (class "Default")
      (node (ref "1") (pin "18") (pinfunction "-VOUT_18") (pintype "passive"))
    )
    (net (code "98") (name "unconnected-(1-DB0-Pad7)") (class "Default")
      (node (ref "1") (pin "7") (pinfunction "DB0_7") (pintype "passive"))
    )
    (net (code "99") (name "unconnected-(1-DB1-Pad8)") (class "Default")
      (node (ref "1") (pin "8") (pinfunction "DB1_8") (pintype "passive"))
    )
    (net (code "100") (name "unconnected-(1-DB2-Pad9)") (class "Default")
      (node (ref "1") (pin "9") (pinfunction "DB2_9") (pintype "passive"))
    )
    (net (code "101") (name "unconnected-(1-DB3-Pad10)") (class "Default")
      (node (ref "1") (pin "10") (pinfunction "DB3_10") (pintype "passive"))
    )
    (net (code "102") (name "unconnected-(1-DB4-Pad11)") (class "Default")
      (node (ref "1") (pin "11") (pinfunction "DB4_11") (pintype "passive"))
    )
    (net (code "103") (name "unconnected-(1-DB5-Pad12)") (class "Default")
      (node (ref "1") (pin "12") (pinfunction "DB5_12") (pintype "passive"))
    )
    (net (code "104") (name "unconnected-(1-DB6-Pad13)") (class "Default")
      (node (ref "1") (pin "13") (pinfunction "DB6_13") (pintype "passive"))
    )
    (net (code "105") (name "unconnected-(1-DB7-Pad14)") (class "Default")
      (node (ref "1") (pin "14") (pinfunction "DB7_14") (pintype "passive"))
    )
    (net (code "106") (name "unconnected-(1-NC-Pad16)") (class "Default")
      (node (ref "1") (pin "16") (pinfunction "NC_16") (pintype "passive"))
    )
    (net (code "107") (name "unconnected-(1-V0-Pad3)") (class "Default")
      (node (ref "1") (pin "3") (pinfunction "V0_3") (pintype "passive"))
    )
    (net (code "108") (name "unconnected-(D7-Pad2)") (class "Default")
      (node (ref "D7") (pin "2") (pinfunction "2_2") (pintype "passive"))
    )
    (net (code "109") (name "unconnected-(H1-Pad0)") (class "Default")
      (node (ref "H1") (pin "0") (pinfunction "0_0") (pintype "passive"))
    )
    (net (code "110") (name "unconnected-(H2-Pad0)") (class "Default")
      (node (ref "H2") (pin "0") (pinfunction "0_0") (pintype "passive"))
    )
    (net (code "111") (name "unconnected-(H3-Pad0)") (class "Default")
      (node (ref "H3") (pin "0") (pinfunction "0_0") (pintype "passive"))
    )
    (net (code "112") (name "unconnected-(H4-Pad0)") (class "Default")
      (node (ref "H4") (pin "0") (pinfunction "0_0") (pintype "passive"))
    )
    (net (code "113") (name "unconnected-(J1-Pad1)") (class "Default")
      (node (ref "J1") (pin "1") (pinfunction "1_1") (pintype "passive"))
    )
    (net (code "114") (name "unconnected-(J1-Pad2)") (class "Default")
      (node (ref "J1") (pin "2") (pinfunction "2_2") (pintype "passive"))
    )
    (net (code "115") (name "unconnected-(J1-Pad3)") (class "Default")
      (node (ref "J1") (pin "3") (pinfunction "3_3") (pintype "passive"))
    )
    (net (code "116") (name "unconnected-(J1-Pad4)") (class "Default")
      (node (ref "J1") (pin "4") (pinfunction "4_4") (pintype "passive"))
    )
    (net (code "117") (name "unconnected-(J1-Pad8)") (class "Default")
      (node (ref "J1") (pin "8") (pinfunction "8_8") (pintype "passive"))
    )
    (net (code "118") (name "unconnected-(J1-Pad9)") (class "Default")
      (node (ref "J1") (pin "9") (pinfunction "9_9") (pintype "passive"))
    )
    (net (code "119") (name "unconnected-(P7-Pad11)") (class "Default")
      (node (ref "P7") (pin "11") (pinfunction "11_11") (pintype "passive"))
    )
    (net (code "120") (name "unconnected-(P7-Pad17)") (class "Default")
      (node (ref "P7") (pin "17") (pinfunction "17_17") (pintype "passive"))
    )
    (net (code "121") (name "unconnected-(P7-Pad19)") (class "Default")
      (node (ref "P7") (pin "19") (pinfunction "19_19") (pintype "passive"))
    )
    (net (code "122") (name "unconnected-(S1-NO1-Pad3A)") (class "Default")
      (node (ref "S1") (pin "3A") (pinfunction "NO1_3A") (pintype "passive"))
    )
    (net (code "123") (name "unconnected-(S1-NO2-Pad3B)") (class "Default")
      (node (ref "S1") (pin "3B") (pinfunction "NO2_3B") (pintype "passive"))
    )
    (net (code "124") (name "unconnected-(U3-NC-Pad73)") (class "Default")
      (node (ref "U3") (pin "73") (pinfunction "NC_73") (pintype "passive"))
    )
    (net (code "125") (name "unconnected-(U3-PC3{slash}ADC13-Pad18)") (class "Default")
      (node (ref "U3") (pin "18") (pinfunction "PC3/ADC13_18") (pintype "passive"))
    )
    (net (code "126") (name "unconnected-(U3-PC13{slash}TAMPER-RTC-Pad7)") (class "Default")
      (node (ref "U3") (pin "7") (pinfunction "PC13/TAMPER-RTC_7") (pintype "passive"))
    )
    (net (code "127") (name "unconnected-(U3-PD0{slash}OSCIN-Pad81)") (class "Default")
      (node (ref "U3") (pin "81") (pinfunction "PD0/OSCIN_81") (pintype "passive"))
    )
    (net (code "128") (name "unconnected-(U3-PD1{slash}OSCOUT-Pad82)") (class "Default")
      (node (ref "U3") (pin "82") (pinfunction "PD1/OSCOUT_82") (pintype "passive"))
    )
    (net (code "129") (name "unconnected-(U3-PD2{slash}TIM3_ETR{slash}U5_RX{slash}SDIO_CMD-Pad83)") (class "Default")
      (node (ref "U3") (pin "83") (pinfunction "PD2/TIM3_ETR/U5_RX/SDIO_CMD_83") (pintype "passive"))
    )
    (net (code "130") (name "unconnected-(U3-PD3-Pad84)") (class "Default")
      (node (ref "U3") (pin "84") (pinfunction "PD3_84") (pintype "passive"))
    )
    (net (code "131") (name "unconnected-(U3-PD4-Pad85)") (class "Default")
      (node (ref "U3") (pin "85") (pinfunction "PD4_85") (pintype "passive"))
    )
    (net (code "132") (name "unconnected-(U3-PD5-Pad86)") (class "Default")
      (node (ref "U3") (pin "86") (pinfunction "PD5_86") (pintype "passive"))
    )
    (net (code "133") (name "unconnected-(U3-PD6-Pad87)") (class "Default")
      (node (ref "U3") (pin "87") (pinfunction "PD6_87") (pintype "passive"))
    )
    (net (code "134") (name "unconnected-(U3-PD7-Pad88)") (class "Default")
      (node (ref "U3") (pin "88") (pinfunction "PD7_88") (pintype "passive"))
    )
    (net (code "135") (name "unconnected-(U3-PE3-Pad2)") (class "Default")
      (node (ref "U3") (pin "2") (pinfunction "PE3_2") (pintype "passive"))
    )
    (net (code "136") (name "unconnected-(U3-PE4-Pad3)") (class "Default")
      (node (ref "U3") (pin "3") (pinfunction "PE4_3") (pintype "passive"))
    )
    (net (code "137") (name "unconnected-(U3-PE5-Pad4)") (class "Default")
      (node (ref "U3") (pin "4") (pinfunction "PE5_4") (pintype "passive"))
    )
    (net (code "138") (name "unconnected-(U3-PE6-Pad5)") (class "Default")
      (node (ref "U3") (pin "5") (pinfunction "PE6_5") (pintype "passive"))
    )
    (net (code "139") (name "unconnected-(U4-1C__in-Pad13)") (class "Default")
      (node (ref "U4") (pin "13") (pinfunction "1C__in_13") (pintype "passive"))
    )
    (net (code "140") (name "unconnected-(U4-1Cout-Pad14)") (class "Default")
      (node (ref "U4") (pin "14") (pinfunction "1Cout_14") (pintype "passive"))
    )
    (net (code "141") (name "unconnected-(U4-151__in-Pad11)") (class "Default")
      (node (ref "U4") (pin "11") (pinfunction "151__in_11") (pintype "passive"))
    )
    (net (code "142") (name "unconnected-(U4-151out-Pad12)") (class "Default")
      (node (ref "U4") (pin "12") (pinfunction "151out_12") (pintype "passive"))
    )
  )
)
